# Connectors.net
KiCad netlist of a schematic drawn in Altium Designer
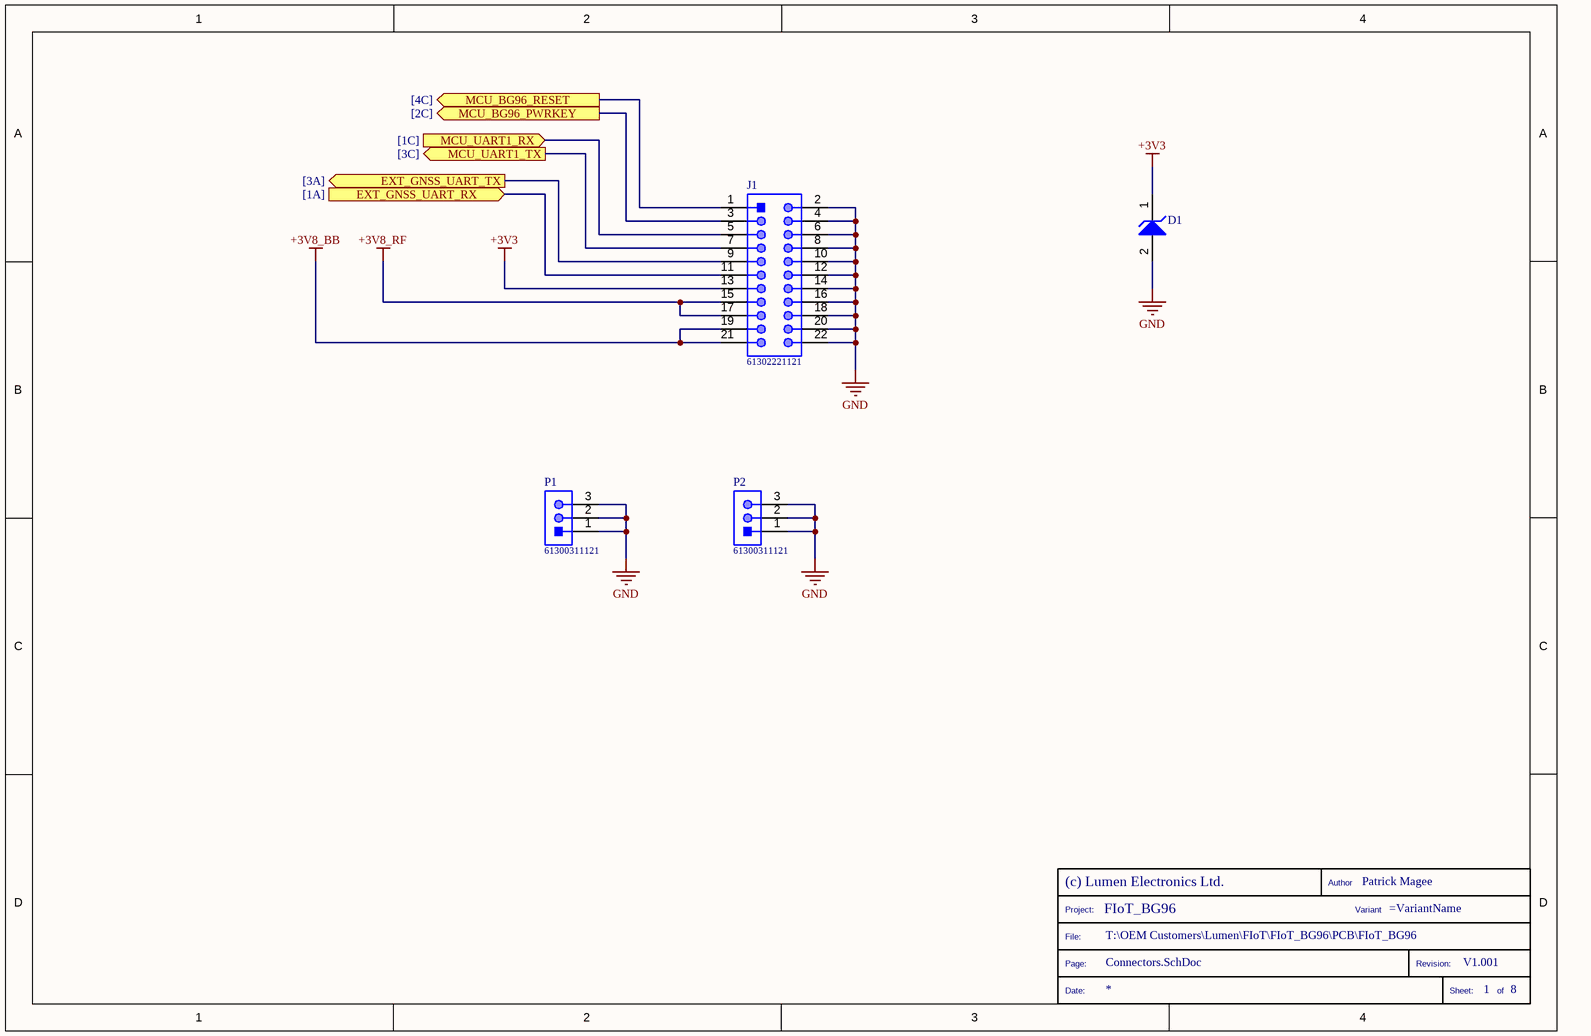
[diagram p0: Connectors.SchDoc]

(export (version "E")
  (design (tool "Eeschema 10.0.6"))
  (components
    (comp (ref "*") (value "TitleBlock") (libsource (lib "FIoT_BG96") (part "TitleBlock")))
    (comp (ref "D1")
      (value "ESD9X3.3ST5G")
      (footprint "ONSC-SOD-923-2-514AA-01_V")
      (fields (field (name "LUMEN PART NUMBER") "LPN00013"))
      (libsource (lib "Lumen") (part "ESD9X3.3ST5G"))
    )
    (comp (ref "J1")
      (value "61302221121")
      (footprint "61302221121")
      (description "THT Vertical Pin Header WR-PHD, Pitch 2.54 mm, Dual Row, 22 pins")
      (fields (field (name "LUMEN PART NUMBER") "LPN00011"))
      (libsource (lib "Lumen") (part "CMP-1502-01108-1"))
    )
    (comp (ref "P1")
      (value "61300311121")
      (footprint "61300311121")
      (description "THT Vertical Pin Header WR-PHD, Pitch 2.54 mm, Single Row, 3 pins")
      (fields (field (name "LUMEN PART NUMBER") "LPN00010"))
      (libsource (lib "Lumen") (part "CMP-1502-01062-1"))
    )
    (comp (ref "P2")
      (value "61300311121")
      (footprint "61300311121")
      (description "THT Vertical Pin Header WR-PHD, Pitch 2.54 mm, Single Row, 3 pins")
      (fields (field (name "LUMEN PART NUMBER") "LPN00010"))
      (libsource (lib "Lumen") (part "CMP-1502-01062-1"))
    )
  )
  (nets
    (net (code "1") (name "+3V3") (class "Default")
      (node (ref "D1") (pin "1") (pinfunction "K_1") (pintype "passive"))
      (node (ref "J1") (pin "13") (pinfunction "13_13") (pintype "passive"))
    )
    (net (code "2") (name "+3V8_BB") (class "Default")
      (node (ref "J1") (pin "19") (pinfunction "19_19") (pintype "passive"))
      (node (ref "J1") (pin "21") (pinfunction "21_21") (pintype "passive"))
    )
    (net (code "3") (name "+3V8_RF") (class "Default")
      (node (ref "J1") (pin "15") (pinfunction "15_15") (pintype "passive"))
      (node (ref "J1") (pin "17") (pinfunction "17_17") (pintype "passive"))
    )
    (net (code "4") (name "/EXT_GNSS_UART_RX") (class "Default")
      (node (ref "J1") (pin "11") (pinfunction "11_11") (pintype "passive"))
    )
    (net (code "5") (name "/EXT_GNSS_UART_TX") (class "Default")
      (node (ref "J1") (pin "9") (pinfunction "9_9") (pintype "passive"))
    )
    (net (code "6") (name "/MCU_BG96_PWRKEY") (class "Default")
      (node (ref "J1") (pin "3") (pinfunction "3_3") (pintype "passive"))
    )
    (net (code "7") (name "/MCU_BG96_RESET") (class "Default")
      (node (ref "J1") (pin "1") (pinfunction "1_1") (pintype "passive"))
    )
    (net (code "8") (name "/MCU_UART1_RX") (class "Default")
      (node (ref "J1") (pin "5") (pinfunction "5_5") (pintype "passive"))
    )
    (net (code "9") (name "/MCU_UART1_TX") (class "Default")
      (node (ref "J1") (pin "7") (pinfunction "7_7") (pintype "passive"))
    )
    (net (code "10") (name "GND") (class "Default")
      (node (ref "D1") (pin "2") (pinfunction "A_2") (pintype "passive"))
      (node (ref "J1") (pin "10") (pinfunction "10_10") (pintype "passive"))
      (node (ref "J1") (pin "12") (pinfunction "12_12") (pintype "passive"))
      (node (ref "J1") (pin "14") (pinfunction "14_14") (pintype "passive"))
      (node (ref "J1") (pin "16") (pinfunction "16_16") (pintype "passive"))
      (node (ref "J1") (pin "18") (pinfunction "18_18") (pintype "passive"))
      (node (ref "J1") (pin "2") (pinfunction "2_2") (pintype "passive"))
      (node (ref "J1") (pin "20") (pinfunction "20_20") (pintype "passive"))
      (node (ref "J1") (pin "22") (pinfunction "22_22") (pintype "passive"))
      (node (ref "J1") (pin "4") (pinfunction "4_4") (pintype "passive"))
      (node (ref "J1") (pin "6") (pinfunction "6_6") (pintype "passive"))
      (node (ref "J1") (pin "8") (pinfunction "8_8") (pintype "passive"))
      (node (ref "P1") (pin "1") (pinfunction "1_1") (pintype "passive"))
      (node (ref "P1") (pin "2") (pinfunction "2_2") (pintype "passive"))
      (node (ref "P1") (pin "3") (pinfunction "3_3") (pintype "passive"))
      (node (ref "P2") (pin "1") (pinfunction "1_1") (pintype "passive"))
      (node (ref "P2") (pin "2") (pinfunction "2_2") (pintype "passive"))
      (node (ref "P2") (pin "3") (pinfunction "3_3") (pintype "passive"))
    )
  )
)
